# WdParent.net
KiCad netlist of a schematic drawn in EAGLE
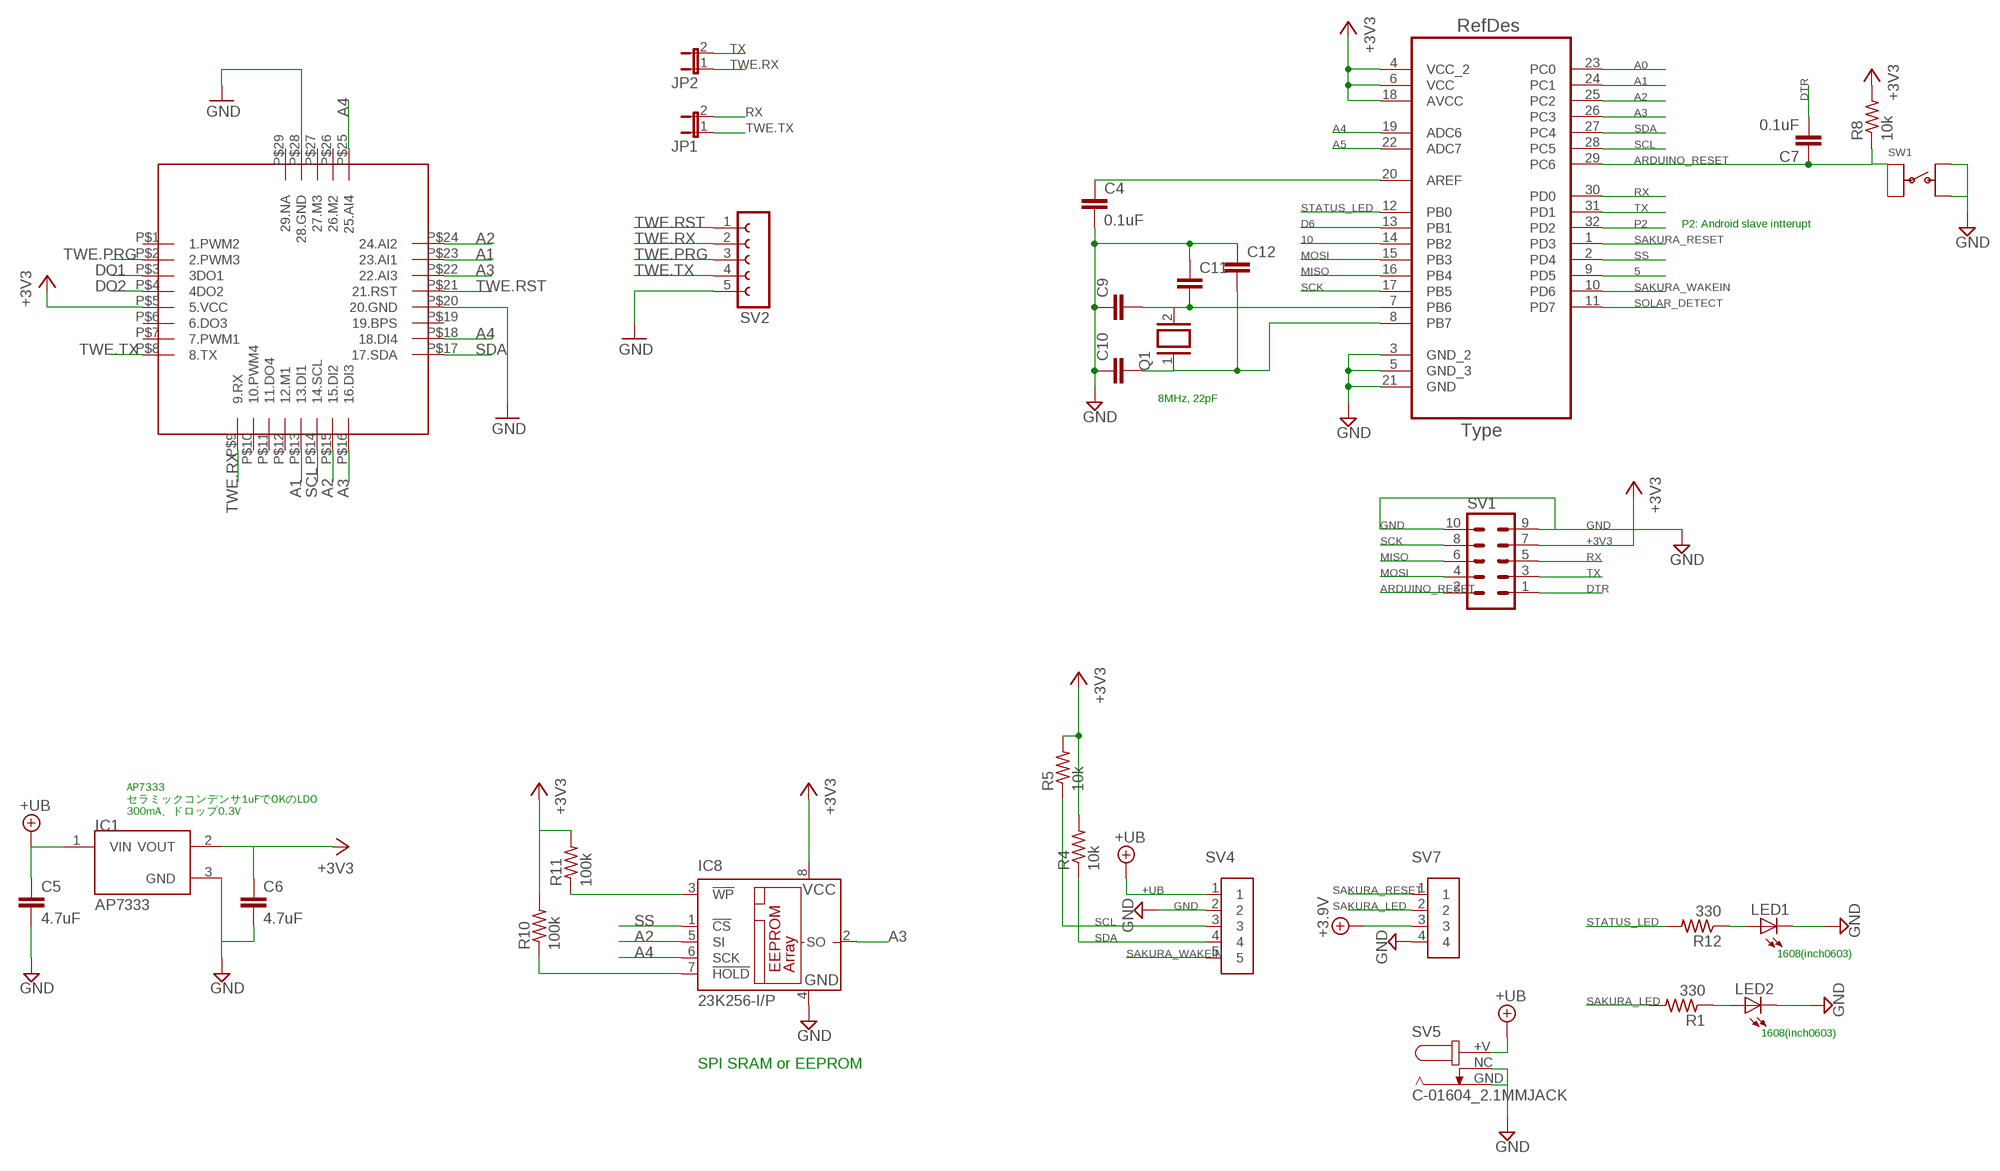
[diagram p0: schematic, sheet 1]

(export (version "E")
  (design (tool "Eeschema 10.0.6"))
  (components
    (comp (ref "C4")
      (value "0.1uF")
      (footprint "eagle-import:C0603")
      (libsource (lib "eagle-import") (part "C-EUC0603"))
    )
    (comp (ref "C5")
      (value "4.7uF")
      (footprint "eagle-import:C0603")
      (libsource (lib "eagle-import") (part "C-EUC0603"))
    )
    (comp (ref "C6")
      (value "4.7uF")
      (footprint "eagle-import:C0603")
      (libsource (lib "eagle-import") (part "C-EUC0603"))
    )
    (comp (ref "C7")
      (value "0.1uF")
      (footprint "eagle-import:C0603")
      (libsource (lib "eagle-import") (part "C-EUC0603"))
    )
    (comp (ref "C9")
      (value "C-EU025-025X050")
      (footprint "eagle-import:C025-025X050")
      (libsource (lib "eagle-import") (part "C-EU025-025X050"))
    )
    (comp (ref "C10")
      (value "C-EU025-025X050")
      (footprint "eagle-import:C025-025X050")
      (libsource (lib "eagle-import") (part "C-EU025-025X050"))
    )
    (comp (ref "C11")
      (value "C-EUC0603")
      (footprint "eagle-import:C0603")
      (libsource (lib "eagle-import") (part "C-EUC0603"))
    )
    (comp (ref "C12")
      (value "C-EUC0603")
      (footprint "eagle-import:C0603")
      (libsource (lib "eagle-import") (part "C-EUC0603"))
    )
    (comp (ref "IC1")
      (value "AP7333")
      (footprint "eagle-import:SOT23")
      (libsource (lib "eagle-import") (part "I-11360_AP7333_LDO3V3_REG"))
    )
    (comp (ref "IC8")
      (value "23K256-I/P")
      (footprint "eagle-import:DIL8")
      (fields (field (name "MF") "MICROCHIP") (field (name "MPN") "25AA040-I/P"))
      (libsource (lib "eagle-import") (part "25PAA040"))
    )
    (comp (ref "JP1")
      (value "JP1E")
      (footprint "eagle-import:JP1")
      (libsource (lib "eagle-import") (part "JP1E"))
    )
    (comp (ref "JP2")
      (value "JP1E")
      (footprint "eagle-import:JP1")
      (libsource (lib "eagle-import") (part "JP1E"))
    )
    (comp (ref "LED1")
      (value "LEDCHIPLED_0603")
      (footprint "eagle-import:CHIPLED_0603")
      (libsource (lib "eagle-import") (part "LEDCHIPLED_0603"))
    )
    (comp (ref "LED2")
      (value "LEDCHIPLED_0603")
      (footprint "eagle-import:CHIPLED_0603")
      (libsource (lib "eagle-import") (part "LEDCHIPLED_0603"))
    )
    (comp (ref "Q1")
      (value "XTAL/S")
      (footprint "eagle-import:QS")
      (libsource (lib "eagle-import") (part "XTAL/S"))
    )
    (comp (ref "R1")
      (value "330")
      (footprint "eagle-import:R0603")
      (libsource (lib "eagle-import") (part "R-US_R0603"))
    )
    (comp (ref "R4")
      (value "10k")
      (footprint "eagle-import:R0603")
      (libsource (lib "eagle-import") (part "R-US_R0603"))
    )
    (comp (ref "R5")
      (value "10k")
      (footprint "eagle-import:R0603")
      (libsource (lib "eagle-import") (part "R-US_R0603"))
    )
    (comp (ref "R8")
      (value "10k")
      (footprint "eagle-import:R0603")
      (libsource (lib "eagle-import") (part "R-US_R0603"))
    )
    (comp (ref "R10")
      (value "100k")
      (footprint "eagle-import:R0603")
      (libsource (lib "eagle-import") (part "R-US_R0603"))
    )
    (comp (ref "R11")
      (value "100k")
      (footprint "eagle-import:R0603")
      (libsource (lib "eagle-import") (part "R-US_R0603"))
    )
    (comp (ref "R12")
      (value "330")
      (footprint "eagle-import:R0603")
      (libsource (lib "eagle-import") (part "R-US_R0603"))
    )
    (comp (ref "SV1")
      (value "MA05-2")
      (footprint "eagle-import:MA05-2")
      (libsource (lib "eagle-import") (part "MA05-2"))
    )
    (comp (ref "SV2")
      (value "FE05-1")
      (footprint "eagle-import:FE05-1")
      (libsource (lib "eagle-import") (part "FE05-1"))
    )
    (comp (ref "SV4")
      (value "PINHEADER_5_2.54MM")
      (footprint "eagle-import:PINHEADER_5_2.54MM")
      (libsource (lib "eagle-import") (part "PINHEADER_5_2.54MM"))
    )
    (comp (ref "SV5")
      (value "C-01604_2.1MMJACK")
      (footprint "eagle-import:2.1MMJACK_SLIM")
      (libsource (lib "eagle-import") (part "C-01604_2.1MMJACK"))
    )
    (comp (ref "SV7")
      (value "PINHEADER_4_2.54MM")
      (footprint "eagle-import:PINHEADER_4_2.54MM")
      (libsource (lib "eagle-import") (part "PINHEADER_4_2.54MM"))
    )
    (comp (ref "SW1")
      (value "TACT_SWITCH")
      (footprint "eagle-import:TACT_SWITCH")
      (libsource (lib "eagle-import") (part "TACT_SWITCH"))
    )
    (comp (ref "U$1")
      (value "LITE")
      (footprint "eagle-import:LITE")
      (libsource (lib "eagle-import") (part "LITE"))
    )
    (comp (ref "U1")
      (value "ATMEGA328P-AU")
      (footprint "eagle-import:QFP80P900X900X120-32N")
      (libsource (lib "eagle-import") (part "ATMEGA328P-AU"))
    )
  )
  (nets
    (net (code "1") (name "+3.9V") (class "Default")
      (node (ref "SV7") (pin "3") (pinfunction "3_3") (pintype "bidirectional"))
    )
    (net (code "2") (name "+3V3") (class "Default")
      (node (ref "C6") (pin "1") (pinfunction "1_1") (pintype "passive"))
      (node (ref "IC1") (pin "2") (pinfunction "VOUT_2") (pintype "bidirectional"))
      (node (ref "IC8") (pin "8") (pinfunction "VCC_8") (pintype "power_in"))
      (node (ref "R10") (pin "2") (pinfunction "2_2") (pintype "passive"))
      (node (ref "R11") (pin "2") (pinfunction "2_2") (pintype "passive"))
      (node (ref "R4") (pin "2") (pinfunction "2_2") (pintype "passive"))
      (node (ref "R5") (pin "2") (pinfunction "2_2") (pintype "passive"))
      (node (ref "R8") (pin "2") (pinfunction "2_2") (pintype "passive"))
      (node (ref "SV1") (pin "7") (pinfunction "7_7") (pintype "passive"))
      (node (ref "U$1") (pin "P$5") (pinfunction "5.VCC_P$5") (pintype "bidirectional"))
      (node (ref "U1") (pin "18") (pinfunction "AVCC_18") (pintype "power_in"))
      (node (ref "U1") (pin "4") (pinfunction "VCC_2_4") (pintype "power_in"))
      (node (ref "U1") (pin "6") (pinfunction "VCC_6") (pintype "power_in"))
    )
    (net (code "3") (name "+UB") (class "Default")
      (node (ref "C5") (pin "1") (pinfunction "1_1") (pintype "passive"))
      (node (ref "IC1") (pin "1") (pinfunction "VIN_1") (pintype "bidirectional"))
      (node (ref "SV4") (pin "1") (pinfunction "1_1") (pintype "bidirectional"))
      (node (ref "SV5") (pin "+V") (pinfunction "VCC_+V") (pintype "passive"))
    )
    (net (code "4") (name "/5") (class "Default")
      (node (ref "U1") (pin "9") (pinfunction "PD5_9") (pintype "bidirectional"))
    )
    (net (code "5") (name "/10") (class "Default")
      (node (ref "U1") (pin "14") (pinfunction "PB2_14") (pintype "bidirectional"))
    )
    (net (code "6") (name "/A0") (class "Default")
      (node (ref "U1") (pin "23") (pinfunction "PC0_23") (pintype "bidirectional"))
    )
    (net (code "7") (name "/A1") (class "Default")
      (node (ref "U$1") (pin "P$13") (pinfunction "13.DI1_P$13") (pintype "bidirectional"))
      (node (ref "U$1") (pin "P$23") (pinfunction "23.AI1_P$23") (pintype "bidirectional"))
      (node (ref "U1") (pin "24") (pinfunction "PC1_24") (pintype "bidirectional"))
    )
    (net (code "8") (name "/A2") (class "Default")
      (node (ref "IC8") (pin "5") (pinfunction "SI_5") (pintype "input"))
      (node (ref "U$1") (pin "P$15") (pinfunction "15.DI2_P$15") (pintype "bidirectional"))
      (node (ref "U$1") (pin "P$24") (pinfunction "24.AI2_P$24") (pintype "bidirectional"))
      (node (ref "U1") (pin "25") (pinfunction "PC2_25") (pintype "bidirectional"))
    )
    (net (code "9") (name "/A3") (class "Default")
      (node (ref "IC8") (pin "2") (pinfunction "SO_2") (pintype "bidirectional"))
      (node (ref "U$1") (pin "P$16") (pinfunction "16.DI3_P$16") (pintype "bidirectional"))
      (node (ref "U$1") (pin "P$22") (pinfunction "22.AI3_P$22") (pintype "bidirectional"))
      (node (ref "U1") (pin "26") (pinfunction "PC3_26") (pintype "bidirectional"))
    )
    (net (code "10") (name "/A4") (class "Default")
      (node (ref "IC8") (pin "6") (pinfunction "SCK_6") (pintype "input"))
      (node (ref "U$1") (pin "P$18") (pinfunction "18.DI4_P$18") (pintype "bidirectional"))
      (node (ref "U$1") (pin "P$25") (pinfunction "25.AI4_P$25") (pintype "bidirectional"))
      (node (ref "U1") (pin "19") (pinfunction "ADC6_19") (pintype "input"))
    )
    (net (code "11") (name "/A5") (class "Default")
      (node (ref "U1") (pin "22") (pinfunction "ADC7_22") (pintype "input"))
    )
    (net (code "12") (name "/ARDUINO_RESET") (class "Default")
      (node (ref "C7") (pin "1") (pinfunction "1_1") (pintype "passive"))
      (node (ref "R8") (pin "1") (pinfunction "1_1") (pintype "passive"))
      (node (ref "SV1") (pin "2") (pinfunction "2_2") (pintype "passive"))
      (node (ref "SW1") (pin "1") (pinfunction "1_1") (pintype "bidirectional"))
      (node (ref "SW1") (pin "2") (pinfunction "2_2") (pintype "bidirectional"))
      (node (ref "U1") (pin "29") (pinfunction "PC6_29") (pintype "bidirectional"))
    )
    (net (code "13") (name "/D6") (class "Default")
      (node (ref "U1") (pin "13") (pinfunction "PB1_13") (pintype "bidirectional"))
    )
    (net (code "14") (name "/DO1") (class "Default")
      (node (ref "U$1") (pin "P$3") (pinfunction "3DO1_P$3") (pintype "bidirectional"))
    )
    (net (code "15") (name "/DO2") (class "Default")
      (node (ref "U$1") (pin "P$4") (pinfunction "4DO2_P$4") (pintype "bidirectional"))
    )
    (net (code "16") (name "/DTR") (class "Default")
      (node (ref "C7") (pin "2") (pinfunction "2_2") (pintype "passive"))
      (node (ref "SV1") (pin "1") (pinfunction "1_1") (pintype "passive"))
    )
    (net (code "17") (name "/MISO") (class "Default")
      (node (ref "SV1") (pin "6") (pinfunction "6_6") (pintype "passive"))
      (node (ref "U1") (pin "16") (pinfunction "PB4_16") (pintype "bidirectional"))
    )
    (net (code "18") (name "/MOSI") (class "Default")
      (node (ref "SV1") (pin "4") (pinfunction "4_4") (pintype "passive"))
      (node (ref "U1") (pin "15") (pinfunction "PB3_15") (pintype "bidirectional"))
    )
    (net (code "19") (name "/P2") (class "Default")
      (node (ref "U1") (pin "32") (pinfunction "PD2_32") (pintype "bidirectional"))
    )
    (net (code "20") (name "/RX") (class "Default")
      (node (ref "JP1") (pin "2") (pinfunction "2_2") (pintype "passive"))
      (node (ref "SV1") (pin "5") (pinfunction "5_5") (pintype "passive"))
      (node (ref "U1") (pin "30") (pinfunction "PD0_30") (pintype "bidirectional"))
    )
    (net (code "21") (name "/SAKURA_LED") (class "Default")
      (node (ref "R1") (pin "2") (pinfunction "2_2") (pintype "passive"))
      (node (ref "SV7") (pin "2") (pinfunction "2_2") (pintype "bidirectional"))
    )
    (net (code "22") (name "/SAKURA_RESET") (class "Default")
      (node (ref "SV7") (pin "1") (pinfunction "1_1") (pintype "bidirectional"))
      (node (ref "U1") (pin "1") (pinfunction "PD3_1") (pintype "bidirectional"))
    )
    (net (code "23") (name "/SAKURA_WAKEIN") (class "Default")
      (node (ref "SV4") (pin "5") (pinfunction "5_5") (pintype "bidirectional"))
      (node (ref "U1") (pin "10") (pinfunction "PD6_10") (pintype "bidirectional"))
    )
    (net (code "24") (name "/SCK") (class "Default")
      (node (ref "SV1") (pin "8") (pinfunction "8_8") (pintype "passive"))
      (node (ref "U1") (pin "17") (pinfunction "PB5_17") (pintype "bidirectional"))
    )
    (net (code "25") (name "/SCL") (class "Default")
      (node (ref "R5") (pin "1") (pinfunction "1_1") (pintype "passive"))
      (node (ref "SV4") (pin "3") (pinfunction "3_3") (pintype "bidirectional"))
      (node (ref "U$1") (pin "P$14") (pinfunction "14.SCL_P$14") (pintype "bidirectional"))
      (node (ref "U1") (pin "28") (pinfunction "PC5_28") (pintype "bidirectional"))
    )
    (net (code "26") (name "/SDA") (class "Default")
      (node (ref "R4") (pin "1") (pinfunction "1_1") (pintype "passive"))
      (node (ref "SV4") (pin "4") (pinfunction "4_4") (pintype "bidirectional"))
      (node (ref "U$1") (pin "P$17") (pinfunction "17.SDA_P$17") (pintype "bidirectional"))
      (node (ref "U1") (pin "27") (pinfunction "PC4_27") (pintype "bidirectional"))
    )
    (net (code "27") (name "/SOLAR_DETECT") (class "Default")
      (node (ref "U1") (pin "11") (pinfunction "PD7_11") (pintype "bidirectional"))
    )
    (net (code "28") (name "/SS") (class "Default")
      (node (ref "IC8") (pin "1") (pinfunction "~{CS}_1") (pintype "input"))
      (node (ref "U1") (pin "2") (pinfunction "PD4_2") (pintype "bidirectional"))
    )
    (net (code "29") (name "/STATUS_LED") (class "Default")
      (node (ref "R12") (pin "2") (pinfunction "2_2") (pintype "passive"))
      (node (ref "U1") (pin "12") (pinfunction "PB0_12") (pintype "bidirectional"))
    )
    (net (code "30") (name "/TWE.PRG") (class "Default")
      (node (ref "SV2") (pin "3") (pinfunction "3_3") (pintype "passive"))
      (node (ref "U$1") (pin "P$2") (pinfunction "2.PWM3_P$2") (pintype "bidirectional"))
    )
    (net (code "31") (name "/TWE.RST") (class "Default")
      (node (ref "SV2") (pin "1") (pinfunction "1_1") (pintype "passive"))
      (node (ref "U$1") (pin "P$21") (pinfunction "21.RST_P$21") (pintype "bidirectional"))
    )
    (net (code "32") (name "/TWE.RX") (class "Default")
      (node (ref "JP2") (pin "1") (pinfunction "1_1") (pintype "passive"))
      (node (ref "SV2") (pin "2") (pinfunction "2_2") (pintype "passive"))
      (node (ref "U$1") (pin "P$9") (pinfunction "9.RX_P$9") (pintype "bidirectional"))
    )
    (net (code "33") (name "/TWE.TX") (class "Default")
      (node (ref "JP1") (pin "1") (pinfunction "1_1") (pintype "passive"))
      (node (ref "SV2") (pin "4") (pinfunction "4_4") (pintype "passive"))
      (node (ref "U$1") (pin "P$8") (pinfunction "8.TX_P$8") (pintype "bidirectional"))
    )
    (net (code "34") (name "/TX") (class "Default")
      (node (ref "JP2") (pin "2") (pinfunction "2_2") (pintype "passive"))
      (node (ref "SV1") (pin "3") (pinfunction "3_3") (pintype "passive"))
      (node (ref "U1") (pin "31") (pinfunction "PD1_31") (pintype "bidirectional"))
    )
    (net (code "35") (name "GND") (class "Default")
      (node (ref "C10") (pin "1") (pinfunction "1_1") (pintype "passive"))
      (node (ref "C11") (pin "1") (pinfunction "1_1") (pintype "passive"))
      (node (ref "C12") (pin "1") (pinfunction "1_1") (pintype "passive"))
      (node (ref "C4") (pin "2") (pinfunction "2_2") (pintype "passive"))
      (node (ref "C5") (pin "2") (pinfunction "2_2") (pintype "passive"))
      (node (ref "C6") (pin "2") (pinfunction "2_2") (pintype "passive"))
      (node (ref "C9") (pin "1") (pinfunction "1_1") (pintype "passive"))
      (node (ref "IC1") (pin "3") (pinfunction "GND_3") (pintype "bidirectional"))
      (node (ref "IC8") (pin "4") (pinfunction "GND_4") (pintype "power_in"))
      (node (ref "LED1") (pin "C") (pinfunction "C_C") (pintype "passive"))
      (node (ref "LED2") (pin "C") (pinfunction "C_C") (pintype "passive"))
      (node (ref "SV1") (pin "10") (pinfunction "10_10") (pintype "passive"))
      (node (ref "SV1") (pin "9") (pinfunction "9_9") (pintype "passive"))
      (node (ref "SV2") (pin "5") (pinfunction "5_5") (pintype "passive"))
      (node (ref "SV4") (pin "2") (pinfunction "2_2") (pintype "bidirectional"))
      (node (ref "SV5") (pin "GND") (pinfunction "GND_GND") (pintype "passive"))
      (node (ref "SV5") (pin "NC") (pinfunction "S_NC") (pintype "passive"))
      (node (ref "SV7") (pin "4") (pinfunction "4_4") (pintype "bidirectional"))
      (node (ref "SW1") (pin "3") (pinfunction "3_3") (pintype "bidirectional"))
      (node (ref "SW1") (pin "4") (pinfunction "4_4") (pintype "bidirectional"))
      (node (ref "U$1") (pin "P$20") (pinfunction "20.GND_P$20") (pintype "bidirectional"))
      (node (ref "U$1") (pin "P$28") (pinfunction "28.GND_P$28") (pintype "bidirectional"))
      (node (ref "U1") (pin "21") (pinfunction "GND_21") (pintype "passive"))
      (node (ref "U1") (pin "3") (pinfunction "GND_2_3") (pintype "passive"))
      (node (ref "U1") (pin "5") (pinfunction "GND_3_5") (pintype "passive"))
    )
    (net (code "36") (name "Net-(IC8-~{HOLD})") (class "Default")
      (node (ref "IC8") (pin "7") (pinfunction "~{HOLD}_7") (pintype "input"))
      (node (ref "R10") (pin "1") (pinfunction "1_1") (pintype "passive"))
    )
    (net (code "37") (name "Net-(IC8-~{WP})") (class "Default")
      (node (ref "IC8") (pin "3") (pinfunction "~{WP}_3") (pintype "input"))
      (node (ref "R11") (pin "1") (pinfunction "1_1") (pintype "passive"))
    )
    (net (code "38") (name "Net-(LED1-PadA)") (class "Default")
      (node (ref "LED1") (pin "A") (pinfunction "A_A") (pintype "passive"))
      (node (ref "R12") (pin "1") (pinfunction "1_1") (pintype "passive"))
    )
    (net (code "39") (name "Net-(LED2-PadA)") (class "Default")
      (node (ref "LED2") (pin "A") (pinfunction "A_A") (pintype "passive"))
      (node (ref "R1") (pin "1") (pinfunction "1_1") (pintype "passive"))
    )
    (net (code "40") (name "Net-(U1-AREF)") (class "Default")
      (node (ref "C4") (pin "1") (pinfunction "1_1") (pintype "passive"))
      (node (ref "U1") (pin "20") (pinfunction "AREF_20") (pintype "input"))
    )
    (net (code "41") (name "Net-(U1-PB6)") (class "Default")
      (node (ref "C11") (pin "2") (pinfunction "2_2") (pintype "passive"))
      (node (ref "C9") (pin "2") (pinfunction "2_2") (pintype "passive"))
      (node (ref "Q1") (pin "2") (pinfunction "2_2") (pintype "passive"))
      (node (ref "U1") (pin "7") (pinfunction "PB6_7") (pintype "bidirectional"))
    )
    (net (code "42") (name "Net-(U1-PB7)") (class "Default")
      (node (ref "C10") (pin "2") (pinfunction "2_2") (pintype "passive"))
      (node (ref "C12") (pin "2") (pinfunction "2_2") (pintype "passive"))
      (node (ref "Q1") (pin "1") (pinfunction "1_1") (pintype "passive"))
      (node (ref "U1") (pin "8") (pinfunction "PB7_8") (pintype "bidirectional"))
    )
    (net (code "43") (name "unconnected-(U$1-1.PWM2-PadP$1)") (class "Default")
      (node (ref "U$1") (pin "P$1") (pinfunction "1.PWM2_P$1") (pintype "bidirectional"))
    )
    (net (code "44") (name "unconnected-(U$1-6.DO3-PadP$6)") (class "Default")
      (node (ref "U$1") (pin "P$6") (pinfunction "6.DO3_P$6") (pintype "bidirectional"))
    )
    (net (code "45") (name "unconnected-(U$1-7.PWM1-PadP$7)") (class "Default")
      (node (ref "U$1") (pin "P$7") (pinfunction "7.PWM1_P$7") (pintype "bidirectional"))
    )
    (net (code "46") (name "unconnected-(U$1-10.PWM4-PadP$10)") (class "Default")
      (node (ref "U$1") (pin "P$10") (pinfunction "10.PWM4_P$10") (pintype "bidirectional"))
    )
    (net (code "47") (name "unconnected-(U$1-11.DO4-PadP$11)") (class "Default")
      (node (ref "U$1") (pin "P$11") (pinfunction "11.DO4_P$11") (pintype "bidirectional"))
    )
    (net (code "48") (name "unconnected-(U$1-12.M1-PadP$12)") (class "Default")
      (node (ref "U$1") (pin "P$12") (pinfunction "12.M1_P$12") (pintype "bidirectional"))
    )
    (net (code "49") (name "unconnected-(U$1-19.BPS-PadP$19)") (class "Default")
      (node (ref "U$1") (pin "P$19") (pinfunction "19.BPS_P$19") (pintype "bidirectional"))
    )
    (net (code "50") (name "unconnected-(U$1-26.M2-PadP$26)") (class "Default")
      (node (ref "U$1") (pin "P$26") (pinfunction "26.M2_P$26") (pintype "bidirectional"))
    )
    (net (code "51") (name "unconnected-(U$1-27.M3-PadP$27)") (class "Default")
      (node (ref "U$1") (pin "P$27") (pinfunction "27.M3_P$27") (pintype "bidirectional"))
    )
    (net (code "52") (name "unconnected-(U$1-29.NA-PadP$29)") (class "Default")
      (node (ref "U$1") (pin "P$29") (pinfunction "29.NA_P$29") (pintype "bidirectional"))
    )
  )
)
